# SCH_ICM-42670-P_2024-09-11.net
KiCad netlist of a schematic drawn in EasyEDA
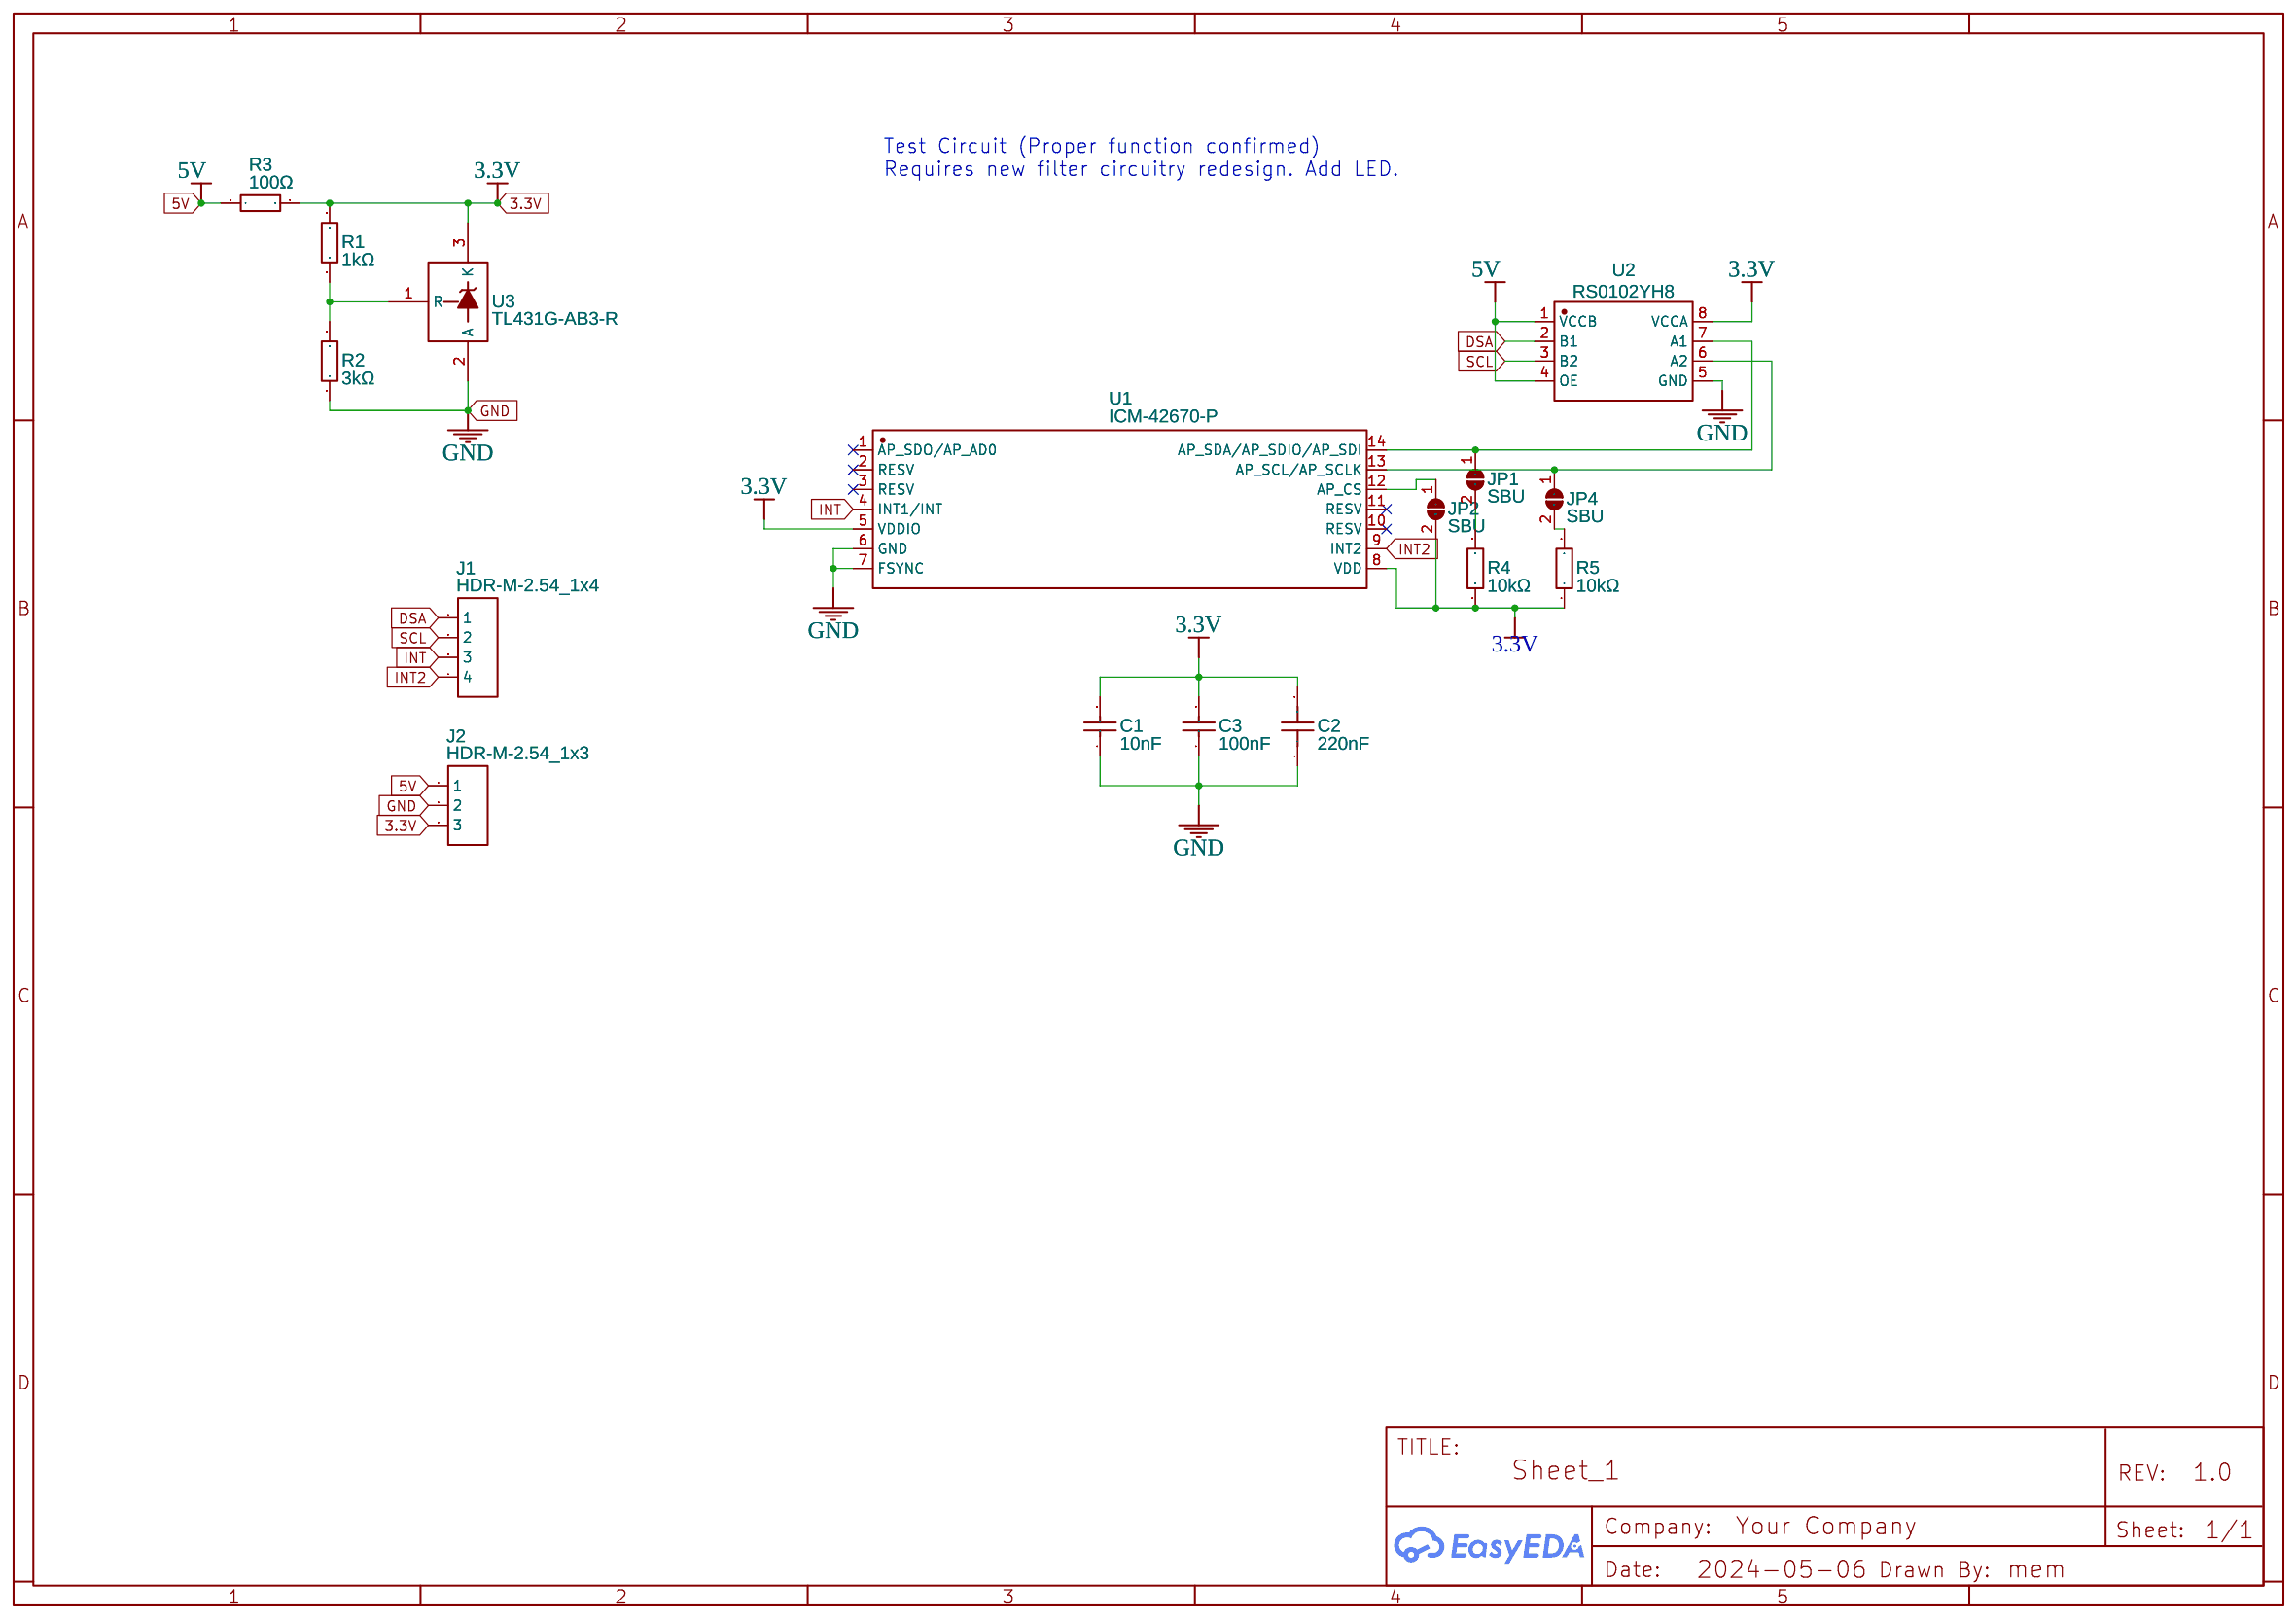
[diagram p0: schematic sheet]

(export (version "E")
  (design (tool "Eeschema 10.0.6"))
  (components
    (comp (ref "C1")
      (value "10nF")
      (fields (field (name "Manufacturer Part") "1206B103K102NT") (field (name "Manufacturer") "FH(风华)"))
      (libsource (lib "") (part "1206B103K102NT"))
    )
    (comp (ref "C2")
      (value "220nF")
      (fields
        (field (name "Manufacturer Part") "TCC1206X7R224K500DT")
        (field (name "Manufacturer") "CCTC(三环)")
      )
      (libsource (lib "") (part "TCC1206X7R224K500DT"))
    )
    (comp (ref "C3")
      (value "100nF")
      (fields (field (name "Manufacturer Part") "1206B104K101NT") (field (name "Manufacturer") "FH(风华)"))
      (libsource (lib "") (part "1206B104K101NT"))
    )
    (comp (ref "J1") (value "HDR-M-2.54_1x4") (libsource (lib "") (part "HDR-M-2.54_1x4")))
    (comp (ref "J2") (value "HDR-M-2.54_1x3") (libsource (lib "") (part "HDR-M-2.54_1x3")))
    (comp (ref "JP1")
      (value "SBU")
      (fields (field (name "Manufacturer Part") "DNP"))
      (libsource (lib "") (part "SBU"))
    )
    (comp (ref "JP2")
      (value "SBU")
      (fields (field (name "Manufacturer Part") "DNP"))
      (libsource (lib "") (part "SBU"))
    )
    (comp (ref "JP4")
      (value "SBU")
      (fields (field (name "Manufacturer Part") "DNP"))
      (libsource (lib "") (part "SBU"))
    )
    (comp (ref "R1")
      (value "1kΩ")
      (fields
        (field (name "Manufacturer Part") "1206W4F1001T5E")
        (field (name "Manufacturer") "UNI-ROYAL(厚声)")
      )
      (libsource (lib "") (part "1206W4F1001T5E"))
    )
    (comp (ref "R2")
      (value "3kΩ")
      (fields
        (field (name "Manufacturer Part") "1206W4F3001T5E")
        (field (name "Manufacturer") "UNI-ROYAL(厚声)")
      )
      (libsource (lib "") (part "1206W4F3001T5E"))
    )
    (comp (ref "R3")
      (value "100Ω")
      (fields
        (field (name "Manufacturer Part") "1206W4F1000T5E")
        (field (name "Manufacturer") "UNI-ROYAL(厚声)")
      )
      (libsource (lib "") (part "1206W4F1000T5E"))
    )
    (comp (ref "R4")
      (value "10kΩ")
      (fields
        (field (name "Manufacturer Part") "1206W4J0103T5E")
        (field (name "Manufacturer") "UNI-ROYAL(厚声)")
      )
      (libsource (lib "") (part "1206W4J0103T5E"))
    )
    (comp (ref "R5")
      (value "10kΩ")
      (fields
        (field (name "Manufacturer Part") "1206W4J0103T5E")
        (field (name "Manufacturer") "UNI-ROYAL(厚声)")
      )
      (libsource (lib "") (part "1206W4J0103T5E"))
    )
    (comp (ref "U1")
      (value "ICM-42670-P")
      (fields (field (name "Manufacturer") "TDK InvenSense(应美盛)"))
      (libsource (lib "") (part "ICM-42670-P"))
    )
    (comp (ref "U2")
      (value "RS0102YH8")
      (fields (field (name "Manufacturer") "RUNIC(润石)"))
      (libsource (lib "") (part "RS0102YH8"))
    )
    (comp (ref "U3")
      (value "TL431G-AB3-R")
      (fields (field (name "Manufacturer") "UTC(友顺)"))
      (libsource (lib "") (part "TL431G-AB3-R"))
    )
  )
  (nets
    (net (code "1") (name "3.3V") (class "Default")
      (node (ref "C1") (pin "2") (pinfunction "2_2") (pintype "input"))
      (node (ref "C2") (pin "2") (pinfunction "2_2") (pintype "unspecified"))
      (node (ref "C3") (pin "2") (pinfunction "2_2") (pintype "input"))
      (node (ref "J2") (pin "3") (pinfunction "3_3") (pintype "input"))
      (node (ref "JP2") (pin "2") (pinfunction "B_2") (pintype "unspecified"))
      (node (ref "R1") (pin "2") (pinfunction "2_2") (pintype "input"))
      (node (ref "R3") (pin "2") (pinfunction "2_2") (pintype "input"))
      (node (ref "R4") (pin "1") (pinfunction "1_1") (pintype "input"))
      (node (ref "R5") (pin "1") (pinfunction "1_1") (pintype "input"))
      (node (ref "U1") (pin "5") (pinfunction "VDDIO_5") (pintype "unspecified"))
      (node (ref "U1") (pin "8") (pinfunction "VDD_8") (pintype "unspecified"))
      (node (ref "U2") (pin "8") (pinfunction "VCCA_8") (pintype "unspecified"))
      (node (ref "U3") (pin "3") (pinfunction "K_3") (pintype "unspecified"))
    )
    (net (code "2") (name "5V") (class "Default")
      (node (ref "J2") (pin "1") (pinfunction "1_1") (pintype "input"))
      (node (ref "R3") (pin "1") (pinfunction "1_1") (pintype "input"))
      (node (ref "U2") (pin "1") (pinfunction "VCCB_1") (pintype "unspecified"))
      (node (ref "U2") (pin "4") (pinfunction "OE_4") (pintype "unspecified"))
    )
    (net (code "3") (name "DSA") (class "Default")
      (node (ref "J1") (pin "1") (pinfunction "1_1") (pintype "unspecified"))
      (node (ref "U2") (pin "2") (pinfunction "B1_2") (pintype "unspecified"))
    )
    (net (code "4") (name "GND") (class "Default")
      (node (ref "C1") (pin "1") (pinfunction "1_1") (pintype "input"))
      (node (ref "C2") (pin "1") (pinfunction "1_1") (pintype "unspecified"))
      (node (ref "C3") (pin "1") (pinfunction "1_1") (pintype "input"))
      (node (ref "J2") (pin "2") (pinfunction "2_2") (pintype "input"))
      (node (ref "R2") (pin "1") (pinfunction "1_1") (pintype "input"))
      (node (ref "U1") (pin "6") (pinfunction "GND_6") (pintype "unspecified"))
      (node (ref "U1") (pin "7") (pinfunction "FSYNC_7") (pintype "unspecified"))
      (node (ref "U2") (pin "5") (pinfunction "GND_5") (pintype "unspecified"))
      (node (ref "U3") (pin "2") (pinfunction "A_2") (pintype "unspecified"))
    )
    (net (code "5") (name "INT") (class "Default")
      (node (ref "J1") (pin "3") (pinfunction "3_3") (pintype "unspecified"))
      (node (ref "U1") (pin "4") (pinfunction "INT1/INT_4") (pintype "unspecified"))
    )
    (net (code "6") (name "INT2") (class "Default")
      (node (ref "J1") (pin "4") (pinfunction "4_4") (pintype "unspecified"))
      (node (ref "U1") (pin "9") (pinfunction "INT2_9") (pintype "unspecified"))
    )
    (net (code "7") (name "Net-(JP1-A)") (class "Default")
      (node (ref "JP1") (pin "1") (pinfunction "A_1") (pintype "unspecified"))
      (node (ref "U1") (pin "14") (pinfunction "AP_SDA/AP_SDIO/AP_SDI_14") (pintype "unspecified"))
      (node (ref "U2") (pin "7") (pinfunction "A1_7") (pintype "unspecified"))
    )
    (net (code "8") (name "Net-(JP1-B)") (class "Default")
      (node (ref "JP1") (pin "2") (pinfunction "B_2") (pintype "unspecified"))
      (node (ref "R4") (pin "2") (pinfunction "2_2") (pintype "input"))
    )
    (net (code "9") (name "Net-(JP2-A)") (class "Default")
      (node (ref "JP2") (pin "1") (pinfunction "A_1") (pintype "unspecified"))
      (node (ref "U1") (pin "12") (pinfunction "AP_CS_12") (pintype "unspecified"))
    )
    (net (code "10") (name "Net-(JP4-A)") (class "Default")
      (node (ref "JP4") (pin "1") (pinfunction "A_1") (pintype "unspecified"))
      (node (ref "U1") (pin "13") (pinfunction "AP_SCL/AP_SCLK_13") (pintype "unspecified"))
      (node (ref "U2") (pin "6") (pinfunction "A2_6") (pintype "unspecified"))
    )
    (net (code "11") (name "Net-(JP4-B)") (class "Default")
      (node (ref "JP4") (pin "2") (pinfunction "B_2") (pintype "unspecified"))
      (node (ref "R5") (pin "2") (pinfunction "2_2") (pintype "input"))
    )
    (net (code "12") (name "Net-(U3-R)") (class "Default")
      (node (ref "R1") (pin "1") (pinfunction "1_1") (pintype "input"))
      (node (ref "R2") (pin "2") (pinfunction "2_2") (pintype "input"))
      (node (ref "U3") (pin "1") (pinfunction "R_1") (pintype "unspecified"))
    )
    (net (code "13") (name "SCL") (class "Default")
      (node (ref "J1") (pin "2") (pinfunction "2_2") (pintype "unspecified"))
      (node (ref "U2") (pin "3") (pinfunction "B2_3") (pintype "unspecified"))
    )
    (net (code "14") (name "unconnected-(U1-AP_SDO{slash}AP_AD0-Pad1)") (class "Default")
      (node (ref "U1") (pin "1") (pinfunction "AP_SDO/AP_AD0_1") (pintype "unspecified+no_connect"))
    )
    (net (code "15") (name "unconnected-(U1-RESV-Pad2)") (class "Default")
      (node (ref "U1") (pin "2") (pinfunction "RESV_2") (pintype "unspecified+no_connect"))
    )
    (net (code "16") (name "unconnected-(U1-RESV-Pad3)") (class "Default")
      (node (ref "U1") (pin "3") (pinfunction "RESV_3") (pintype "unspecified+no_connect"))
    )
    (net (code "17") (name "unconnected-(U1-RESV-Pad10)") (class "Default")
      (node (ref "U1") (pin "10") (pinfunction "RESV_10") (pintype "unspecified+no_connect"))
    )
    (net (code "18") (name "unconnected-(U1-RESV-Pad11)") (class "Default")
      (node (ref "U1") (pin "11") (pinfunction "RESV_11") (pintype "unspecified+no_connect"))
    )
  )
)
